# 4_unextended_ISO_power.net
KiCad netlist of a schematic drawn in Altium Designer
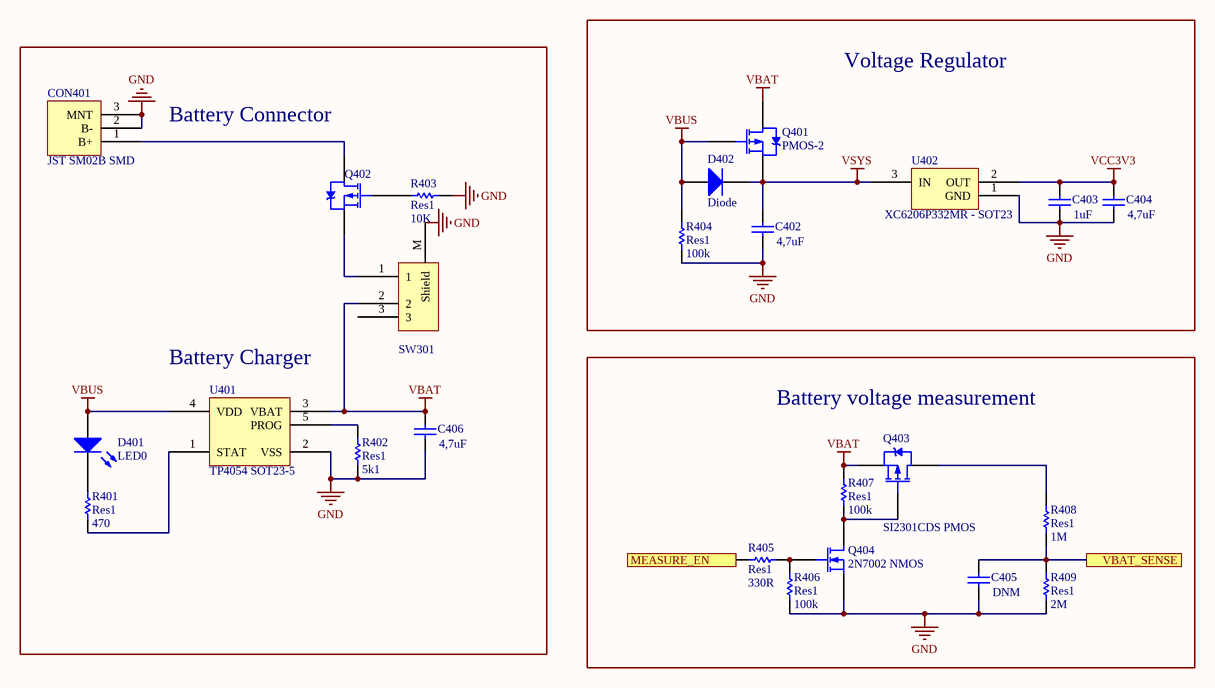
[diagram p0: 4_unextended_ISO_power.SchDoc]

(export (version "E")
  (design (tool "Eeschema 10.0.6"))
  (components
    (comp (ref "C402")
      (value "4,7uF")
      (footprint "C0603[1608]")
      (description "Capacitor")
      (fields (field (name "LCSC PART #") "C19666") (field (name "MRF.PART") "CL10A475KO8NNNC"))
      (libsource (lib "Miscellaneous Devices") (part "Cap"))
    )
    (comp (ref "C403")
      (value "1uF")
      (footprint "C0603[1608]")
      (description "Capacitor")
      (fields (field (name "MFG") "KEMET") (field (name "LCSC PART #") "C15849"))
      (libsource (lib "Miscellaneous Devices") (part "Cap"))
    )
    (comp (ref "C404")
      (value "4,7uF")
      (footprint "C0603[1608]")
      (description "Capacitor")
      (fields (field (name "LCSC PART #") "C19666") (field (name "MRF.PART") "CL10A475KO8NNNC"))
      (libsource (lib "Miscellaneous Devices") (part "Cap"))
    )
    (comp (ref "C405")
      (value "DNM")
      (footprint "C0603[1608]")
      (description "Capacitor")
      (libsource (lib "Miscellaneous Devices") (part "Cap"))
    )
    (comp (ref "C406")
      (value "4,7uF")
      (footprint "C0603[1608]")
      (description "Capacitor")
      (fields (field (name "LCSC PART #") "C19666") (field (name "MRF.PART") "CL10A475KO8NNNC"))
      (libsource (lib "Miscellaneous Devices") (part "Cap"))
    )
    (comp (ref "CON401")
      (value "JST SM02B SMD")
      (footprint "JST S2B-PH-SM4-TB")
      (libsource (lib "Keebs") (part "JST S2B-PH-SM4-TB"))
    )
    (comp (ref "D401")
      (value "LED0")
      (footprint "LED0603[1608]")
      (description "Typical INFRARED GaAs LED")
      (fields (field (name "LCSC PART #") "C72038") (field (name "MRF.PART") "19-213/Y2C-CQ2R2L/3T(CY)"))
      (libsource (lib "Miscellaneous Devices") (part "LED0"))
    )
    (comp (ref "D402")
      (value "Diode")
      (footprint "SOD-123")
      (description "Default Diode")
      (fields (field (name "LCSC PART #") "C8598") (field (name "MRF.PART") "B5819W"))
      (libsource (lib "Miscellaneous Devices") (part "Diode"))
    )
    (comp (ref "Q401")
      (value "PMOS-2")
      (footprint "SOT-23-3")
      (description "P-Channel Power MOSFET")
      (fields (field (name "MRF.PART") "SI2301CDS-T1-GE3") (field (name "LCSC PART #") "C10487"))
      (libsource (lib "Miscellaneous Devices") (part "PMOS-2"))
    )
    (comp (ref "Q402")
      (value "PMOS-2")
      (footprint "SOT-23-3")
      (description "P-Channel Power MOSFET")
      (fields (field (name "LCSC PART #") "C10487") (field (name "MRF.PART") "SI2301CDS-T1-GE3"))
      (libsource (lib "Miscellaneous Devices") (part "PMOS-2"))
    )
    (comp (ref "Q403")
      (value "SI2301CDS PMOS")
      (footprint "SOT-23-3")
      (description "P-Channel Power MOSFET")
      (fields (field (name "MRF.PART") "SI2301CDS-T1-GE3") (field (name "LCSC PART #") "C10487"))
      (libsource (lib "Miscellaneous Devices") (part "PMOS-2"))
    )
    (comp (ref "Q404")
      (value "2N7002 NMOS")
      (footprint "SOT-23-3")
      (description "N-Channel MOSFET")
      (fields (field (name "LCSC PART #") "C8545") (field (name "MRF.PART") "2N7002"))
      (libsource (lib "Miscellaneous Devices") (part "MOSFET-N"))
    )
    (comp (ref "R401")
      (value "Res1")
      (footprint "R0603[1608]")
      (description "Resistor")
      (fields
        (field (name "ALTIUM_VALUE") "470")
        (field (name "MFG") "Panasonic Electronic Components")
        (field (name "LCSC PART #") "C23179")
      )
      (libsource (lib "Miscellaneous Devices") (part "Res1"))
    )
    (comp (ref "R402")
      (value "Res1")
      (footprint "R0603[1608]")
      (description "Resistor")
      (fields
        (field (name "ALTIUM_VALUE") "5k1")
        (field (name "MFG") "Panasonic Electronic Components")
        (field (name "LCSC PART #") "C23186")
      )
      (libsource (lib "Miscellaneous Devices") (part "Res1"))
    )
    (comp (ref "R403")
      (value "Res1")
      (footprint "R0603[1608]")
      (description "Resistor")
      (fields
        (field (name "ALTIUM_VALUE") "10K")
        (field (name "MFG") "Panasonic Electronic Components")
        (field (name "LCSC PART #") "C25804")
      )
      (libsource (lib "Miscellaneous Devices") (part "Res1"))
    )
    (comp (ref "R404")
      (value "Res1")
      (footprint "R0603[1608]")
      (description "Resistor")
      (fields
        (field (name "ALTIUM_VALUE") "100k")
        (field (name "MRF.PART") "0603WAF1003T5E")
        (field (name "LCSC PART #") "C25803")
      )
      (libsource (lib "Miscellaneous Devices") (part "Res1"))
    )
    (comp (ref "R405")
      (value "Res1")
      (footprint "R0603[1608]")
      (description "Resistor")
      (fields
        (field (name "ALTIUM_VALUE") "330R")
        (field (name "LCSC PART #") "C23138")
        (field (name "MRF.PART") "0603WAF3300T5E")
      )
      (libsource (lib "Miscellaneous Devices") (part "Res1"))
    )
    (comp (ref "R406")
      (value "Res1")
      (footprint "R0603[1608]")
      (description "Resistor")
      (fields
        (field (name "ALTIUM_VALUE") "100k")
        (field (name "MRF.PART") "0603WAF1003T5E")
        (field (name "LCSC PART #") "C25803")
      )
      (libsource (lib "Miscellaneous Devices") (part "Res1"))
    )
    (comp (ref "R407")
      (value "Res1")
      (footprint "R0603[1608]")
      (description "Resistor")
      (fields
        (field (name "ALTIUM_VALUE") "100k")
        (field (name "MRF.PART") "0603WAF1003T5E")
        (field (name "LCSC PART #") "C25803")
      )
      (libsource (lib "Miscellaneous Devices") (part "Res1"))
    )
    (comp (ref "R408")
      (value "Res1")
      (footprint "R0603[1608]")
      (description "Resistor")
      (fields
        (field (name "ALTIUM_VALUE") "1M")
        (field (name "MRF.PART") "0603WAF1004T5E")
        (field (name "LCSC PART #") "C22935")
      )
      (libsource (lib "Miscellaneous Devices") (part "Res1"))
    )
    (comp (ref "R409")
      (value "Res1")
      (footprint "R0603[1608]")
      (description "Resistor")
      (fields
        (field (name "ALTIUM_VALUE") "2M")
        (field (name "MRF.PART") "0603WAF2004T5E")
        (field (name "LCSC PART #") "C22976")
      )
      (libsource (lib "Miscellaneous Devices") (part "Res1"))
    )
    (comp (ref "SW301")
      (value "Korean Hroparts Elec K3-1296S-E2")
      (footprint "Korean Hroparts Elec K3-1296S-E2")
      (fields (field (name "LCSC PART #") "C136659"))
      (libsource (lib "Keebs") (part "Korean Hroparts Elec K3-1296S-E2"))
    )
    (comp (ref "U401")
      (value "TP4054 SOT23-5")
      (footprint "SOT-23-5")
      (fields (field (name "LCSC PART #") "C32574") (field (name "MRF.PART") "TP4054"))
      (libsource (lib "Keebs") (part "MCP73831"))
    )
    (comp (ref "U402")
      (value "XC6206P332MR - SOT23")
      (footprint "SOT-23-3")
      (fields
        (field (name "LCSC PART #") "C5446")
        (field (name "MRF.PART") "XC6206P332MR")
        (field (name "MFG") "Texas Instruments")
      )
      (libsource (lib "Keebs") (part "SOT23 LDO"))
    )
  )
  (nets
    (net (code "1") (name "/MEASURE_EN") (class "Default")
      (node (ref "R405") (pin "1") (pinfunction "1_1") (pintype "passive"))
    )
    (net (code "2") (name "/VBAT_SENSE") (class "Default")
      (node (ref "C405") (pin "2") (pinfunction "2_2") (pintype "passive"))
      (node (ref "R408") (pin "2") (pinfunction "2_2") (pintype "passive"))
      (node (ref "R409") (pin "1") (pinfunction "1_1") (pintype "passive"))
    )
    (net (code "3") (name "GND") (class "Default")
      (node (ref "C402") (pin "1") (pinfunction "1_1") (pintype "passive"))
      (node (ref "C403") (pin "1") (pinfunction "1_1") (pintype "passive"))
      (node (ref "C404") (pin "1") (pinfunction "1_1") (pintype "passive"))
      (node (ref "C405") (pin "1") (pinfunction "1_1") (pintype "passive"))
      (node (ref "C406") (pin "1") (pinfunction "1_1") (pintype "passive"))
      (node (ref "CON401") (pin "2") (pinfunction "B-_2") (pintype "passive"))
      (node (ref "CON401") (pin "3") (pinfunction "MNT_3") (pintype "passive"))
      (node (ref "Q404") (pin "2") (pinfunction "S_2") (pintype "passive"))
      (node (ref "R402") (pin "2") (pinfunction "2_2") (pintype "passive"))
      (node (ref "R403") (pin "2") (pinfunction "2_2") (pintype "passive"))
      (node (ref "R404") (pin "2") (pinfunction "2_2") (pintype "passive"))
      (node (ref "R406") (pin "2") (pinfunction "2_2") (pintype "passive"))
      (node (ref "R409") (pin "2") (pinfunction "2_2") (pintype "passive"))
      (node (ref "SW301") (pin "M") (pinfunction "Shield_M") (pintype "passive"))
      (node (ref "U401") (pin "2") (pinfunction "VSS_2") (pintype "passive"))
      (node (ref "U402") (pin "1") (pinfunction "GND_1") (pintype "passive"))
    )
    (net (code "4") (name "Net-(CON401-B+)") (class "Default")
      (node (ref "CON401") (pin "1") (pinfunction "B+_1") (pintype "passive"))
      (node (ref "Q402") (pin "3") (pinfunction "D_3") (pintype "passive"))
    )
    (net (code "5") (name "Net-(D401-K)") (class "Default")
      (node (ref "D401") (pin "2") (pinfunction "K_2") (pintype "passive"))
      (node (ref "R401") (pin "2") (pinfunction "2_2") (pintype "passive"))
    )
    (net (code "6") (name "Net-(Q402-G)") (class "Default")
      (node (ref "Q402") (pin "1") (pinfunction "G_1") (pintype "passive"))
      (node (ref "R403") (pin "1") (pinfunction "1_1") (pintype "passive"))
    )
    (net (code "7") (name "Net-(Q402-S)") (class "Default")
      (node (ref "Q402") (pin "2") (pinfunction "S_2") (pintype "passive"))
      (node (ref "SW301") (pin "1") (pinfunction "1_1") (pintype "passive"))
    )
    (net (code "8") (name "Net-(Q403-D)") (class "Default")
      (node (ref "Q403") (pin "3") (pinfunction "D_3") (pintype "passive"))
      (node (ref "R408") (pin "1") (pinfunction "1_1") (pintype "passive"))
    )
    (net (code "9") (name "Net-(Q403-G)") (class "Default")
      (node (ref "Q403") (pin "1") (pinfunction "G_1") (pintype "passive"))
      (node (ref "Q404") (pin "3") (pinfunction "D_3") (pintype "passive"))
      (node (ref "R407") (pin "2") (pinfunction "2_2") (pintype "passive"))
    )
    (net (code "10") (name "Net-(Q404-G)") (class "Default")
      (node (ref "Q404") (pin "1") (pinfunction "G_1") (pintype "passive"))
      (node (ref "R405") (pin "2") (pinfunction "2_2") (pintype "passive"))
      (node (ref "R406") (pin "1") (pinfunction "1_1") (pintype "passive"))
    )
    (net (code "11") (name "Net-(U401-PROG)") (class "Default")
      (node (ref "R402") (pin "1") (pinfunction "1_1") (pintype "passive"))
      (node (ref "U401") (pin "5") (pinfunction "PROG_5") (pintype "passive"))
    )
    (net (code "12") (name "Net-(U401-STAT)") (class "Default")
      (node (ref "R401") (pin "1") (pinfunction "1_1") (pintype "passive"))
      (node (ref "U401") (pin "1") (pinfunction "STAT_1") (pintype "passive"))
    )
    (net (code "13") (name "VBAT") (class "Default")
      (node (ref "C406") (pin "2") (pinfunction "2_2") (pintype "passive"))
      (node (ref "Q401") (pin "3") (pinfunction "D_3") (pintype "passive"))
      (node (ref "Q403") (pin "2") (pinfunction "S_2") (pintype "passive"))
      (node (ref "R407") (pin "1") (pinfunction "1_1") (pintype "passive"))
      (node (ref "SW301") (pin "2") (pinfunction "2_2") (pintype "passive"))
      (node (ref "U401") (pin "3") (pinfunction "VBAT_3") (pintype "passive"))
    )
    (net (code "14") (name "VBUS") (class "Default")
      (node (ref "D401") (pin "1") (pinfunction "A_1") (pintype "passive"))
      (node (ref "D402") (pin "1") (pinfunction "A_1") (pintype "passive"))
      (node (ref "Q401") (pin "1") (pinfunction "G_1") (pintype "passive"))
      (node (ref "R404") (pin "1") (pinfunction "1_1") (pintype "passive"))
      (node (ref "U401") (pin "4") (pinfunction "VDD_4") (pintype "passive"))
    )
    (net (code "15") (name "VCC3V3") (class "Default")
      (node (ref "C403") (pin "2") (pinfunction "2_2") (pintype "passive"))
      (node (ref "C404") (pin "2") (pinfunction "2_2") (pintype "passive"))
      (node (ref "U402") (pin "2") (pinfunction "OUT_2") (pintype "passive"))
    )
    (net (code "16") (name "VSYS") (class "Default")
      (node (ref "C402") (pin "2") (pinfunction "2_2") (pintype "passive"))
      (node (ref "D402") (pin "2") (pinfunction "K_2") (pintype "passive"))
      (node (ref "Q401") (pin "2") (pinfunction "S_2") (pintype "passive"))
      (node (ref "U402") (pin "3") (pinfunction "IN_3") (pintype "passive"))
    )
    (net (code "17") (name "unconnected-(SW301-Pad3)") (class "Default")
      (node (ref "SW301") (pin "3") (pinfunction "3_3") (pintype "passive"))
    )
  )
)
